# E17-12-VCU-SIC.net
KiCad netlist of a schematic drawn in Altium Designer
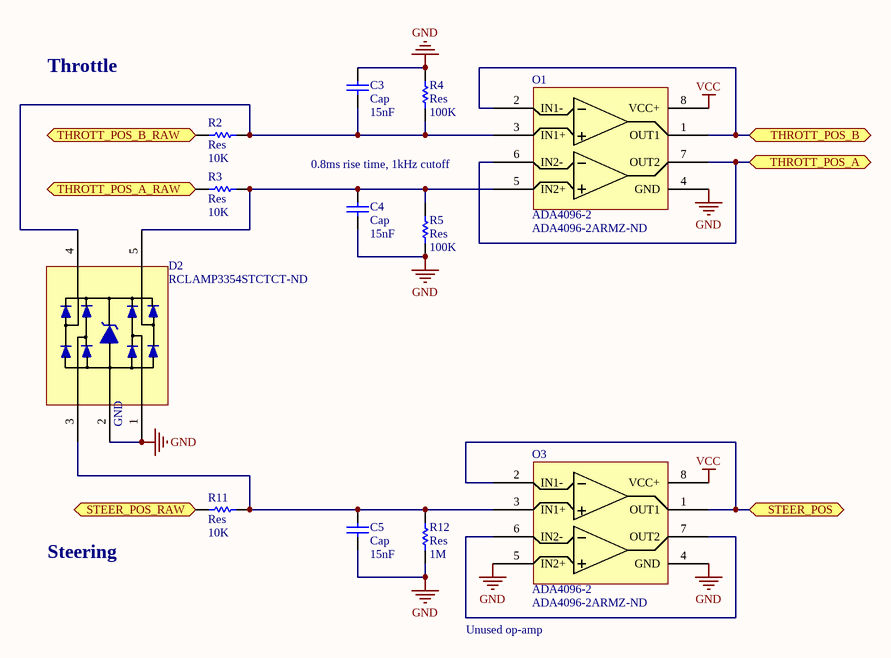
[diagram p0: E17-12-VCU-SIC.SchDoc]

(export (version "E")
  (design (tool "Eeschema 10.0.6"))
  (components
    (comp (ref "C3")
      (value "Cap")
      (footprint "C0805")
      (description "Capacitor")
      (fields (field (name "ALTIUM_VALUE") "15nF") (field (name "PUBLISHER") "Altium Limited"))
      (libsource (lib "Capacitors") (part "Cap"))
    )
    (comp (ref "C4")
      (value "Cap")
      (footprint "C0805")
      (description "Capacitor")
      (fields (field (name "ALTIUM_VALUE") "15nF") (field (name "PUBLISHER") "Altium Limited"))
      (libsource (lib "Capacitors") (part "Cap"))
    )
    (comp (ref "C5")
      (value "Cap")
      (footprint "C0805")
      (description "Capacitor")
      (fields (field (name "ALTIUM_VALUE") "15nF") (field (name "PUBLISHER") "Altium Limited"))
      (libsource (lib "Capacitors") (part "Cap"))
    )
    (comp (ref "D2")
      (value "RCLAMP3354S.TCT")
      (footprint "SOT95P280X145-5N")
      (fields (field (name "SUPPLIER PART NUMBER 1") "RCLAMP3354STCTCT-ND"))
      (libsource (lib "Diodes") (part "RCLAMP3354S.TCT"))
    )
    (comp (ref "O1")
      (value "ADA4096-2")
      (footprint "TSSOP8")
      (description "2 Op-Amps, 8-TSSOP, 32V Overvoltage Protection")
      (fields (field (name "SUPPLIER PART NUMBER 1") "ADA4096-2ARMZ-ND"))
      (libsource (lib "Operational Amplifiers") (part "ADA4096-2"))
    )
    (comp (ref "O3")
      (value "ADA4096-2")
      (footprint "TSSOP8")
      (description "2 Op-Amps, 8-TSSOP, 32V Overvoltage Protection")
      (fields (field (name "SUPPLIER PART NUMBER 1") "ADA4096-2ARMZ-ND"))
      (libsource (lib "Operational Amplifiers") (part "ADA4096-2"))
    )
    (comp (ref "R2")
      (value "Res")
      (footprint "2012[0805]")
      (description "Surface Mount Resistor")
      (fields (field (name "ALTIUM_VALUE") "10K") (field (name "PUBLISHER") "Altium Limited"))
      (libsource (lib "Resistors") (part "Res"))
    )
    (comp (ref "R3")
      (value "Res")
      (footprint "2012[0805]")
      (description "Surface Mount Resistor")
      (fields (field (name "ALTIUM_VALUE") "10K") (field (name "PUBLISHER") "Altium Limited"))
      (libsource (lib "Resistors") (part "Res"))
    )
    (comp (ref "R4")
      (value "Res")
      (footprint "2012[0805]")
      (description "Surface Mount Resistor")
      (fields (field (name "ALTIUM_VALUE") "100K") (field (name "PUBLISHER") "Altium Limited"))
      (libsource (lib "Resistors") (part "Res"))
    )
    (comp (ref "R5")
      (value "Res")
      (footprint "2012[0805]")
      (description "Surface Mount Resistor")
      (fields (field (name "ALTIUM_VALUE") "100K") (field (name "PUBLISHER") "Altium Limited"))
      (libsource (lib "Resistors") (part "Res"))
    )
    (comp (ref "R11")
      (value "Res")
      (footprint "2012[0805]")
      (description "Surface Mount Resistor")
      (fields (field (name "ALTIUM_VALUE") "10K") (field (name "PUBLISHER") "Altium Limited"))
      (libsource (lib "Resistors") (part "Res"))
    )
    (comp (ref "R12")
      (value "Res")
      (footprint "2012[0805]")
      (description "Surface Mount Resistor")
      (fields (field (name "ALTIUM_VALUE") "1M") (field (name "PUBLISHER") "Altium Limited"))
      (libsource (lib "Resistors") (part "Res"))
    )
  )
  (nets
    (net (code "1") (name "/STEER_POS") (class "Default")
      (node (ref "O3") (pin "1") (pinfunction "OUT1_1") (pintype "passive"))
      (node (ref "O3") (pin "2") (pinfunction "IN1-_2") (pintype "passive"))
    )
    (net (code "2") (name "/STEER_POS_RAW") (class "Default")
      (node (ref "R11") (pin "1") (pinfunction "1_1") (pintype "passive"))
    )
    (net (code "3") (name "/THROTT_POS_A") (class "Default")
      (node (ref "O1") (pin "6") (pinfunction "IN2-_6") (pintype "passive"))
      (node (ref "O1") (pin "7") (pinfunction "OUT2_7") (pintype "passive"))
    )
    (net (code "4") (name "/THROTT_POS_A_RAW") (class "Default")
      (node (ref "R3") (pin "2") (pinfunction "2_2") (pintype "passive"))
    )
    (net (code "5") (name "/THROTT_POS_B") (class "Default")
      (node (ref "O1") (pin "1") (pinfunction "OUT1_1") (pintype "passive"))
      (node (ref "O1") (pin "2") (pinfunction "IN1-_2") (pintype "passive"))
    )
    (net (code "6") (name "/THROTT_POS_B_RAW") (class "Default")
      (node (ref "R2") (pin "2") (pinfunction "2_2") (pintype "passive"))
    )
    (net (code "7") (name "GND") (class "Default")
      (node (ref "C3") (pin "1") (pinfunction "1_1") (pintype "passive"))
      (node (ref "C4") (pin "2") (pinfunction "2_2") (pintype "passive"))
      (node (ref "C5") (pin "1") (pinfunction "1_1") (pintype "passive"))
      (node (ref "D2") (pin "1") (pinfunction "1_1") (pintype "passive"))
      (node (ref "D2") (pin "2") (pinfunction "GND_2") (pintype "passive"))
      (node (ref "O1") (pin "4") (pinfunction "GND_4") (pintype "passive"))
      (node (ref "O3") (pin "4") (pinfunction "GND_4") (pintype "passive"))
      (node (ref "O3") (pin "5") (pinfunction "IN2+_5") (pintype "passive"))
      (node (ref "R12") (pin "1") (pinfunction "1_1") (pintype "passive"))
      (node (ref "R4") (pin "2") (pinfunction "2_2") (pintype "passive"))
      (node (ref "R5") (pin "1") (pinfunction "1_1") (pintype "passive"))
    )
    (net (code "8") (name "Net-(O1-IN1+)") (class "Default")
      (node (ref "C3") (pin "2") (pinfunction "2_2") (pintype "passive"))
      (node (ref "D2") (pin "4") (pinfunction "4_4") (pintype "passive"))
      (node (ref "O1") (pin "3") (pinfunction "IN1+_3") (pintype "passive"))
      (node (ref "R2") (pin "1") (pinfunction "1_1") (pintype "passive"))
      (node (ref "R4") (pin "1") (pinfunction "1_1") (pintype "passive"))
    )
    (net (code "9") (name "Net-(O1-IN2+)") (class "Default")
      (node (ref "C4") (pin "1") (pinfunction "1_1") (pintype "passive"))
      (node (ref "D2") (pin "5") (pinfunction "5_5") (pintype "passive"))
      (node (ref "O1") (pin "5") (pinfunction "IN2+_5") (pintype "passive"))
      (node (ref "R3") (pin "1") (pinfunction "1_1") (pintype "passive"))
      (node (ref "R5") (pin "2") (pinfunction "2_2") (pintype "passive"))
    )
    (net (code "10") (name "Net-(O3-IN1+)") (class "Default")
      (node (ref "C5") (pin "2") (pinfunction "2_2") (pintype "passive"))
      (node (ref "D2") (pin "3") (pinfunction "3_3") (pintype "passive"))
      (node (ref "O3") (pin "3") (pinfunction "IN1+_3") (pintype "passive"))
      (node (ref "R11") (pin "2") (pinfunction "2_2") (pintype "passive"))
      (node (ref "R12") (pin "2") (pinfunction "2_2") (pintype "passive"))
    )
    (net (code "11") (name "Net-(O3-IN2-)") (class "Default")
      (node (ref "O3") (pin "6") (pinfunction "IN2-_6") (pintype "passive"))
      (node (ref "O3") (pin "7") (pinfunction "OUT2_7") (pintype "passive"))
    )
    (net (code "12") (name "VCC") (class "Default")
      (node (ref "O1") (pin "8") (pinfunction "VCC+_8") (pintype "passive"))
      (node (ref "O3") (pin "8") (pinfunction "VCC+_8") (pintype "passive"))
    )
  )
)
